# SKYROCKET1.net
KiCad netlist of a schematic drawn in EAGLE
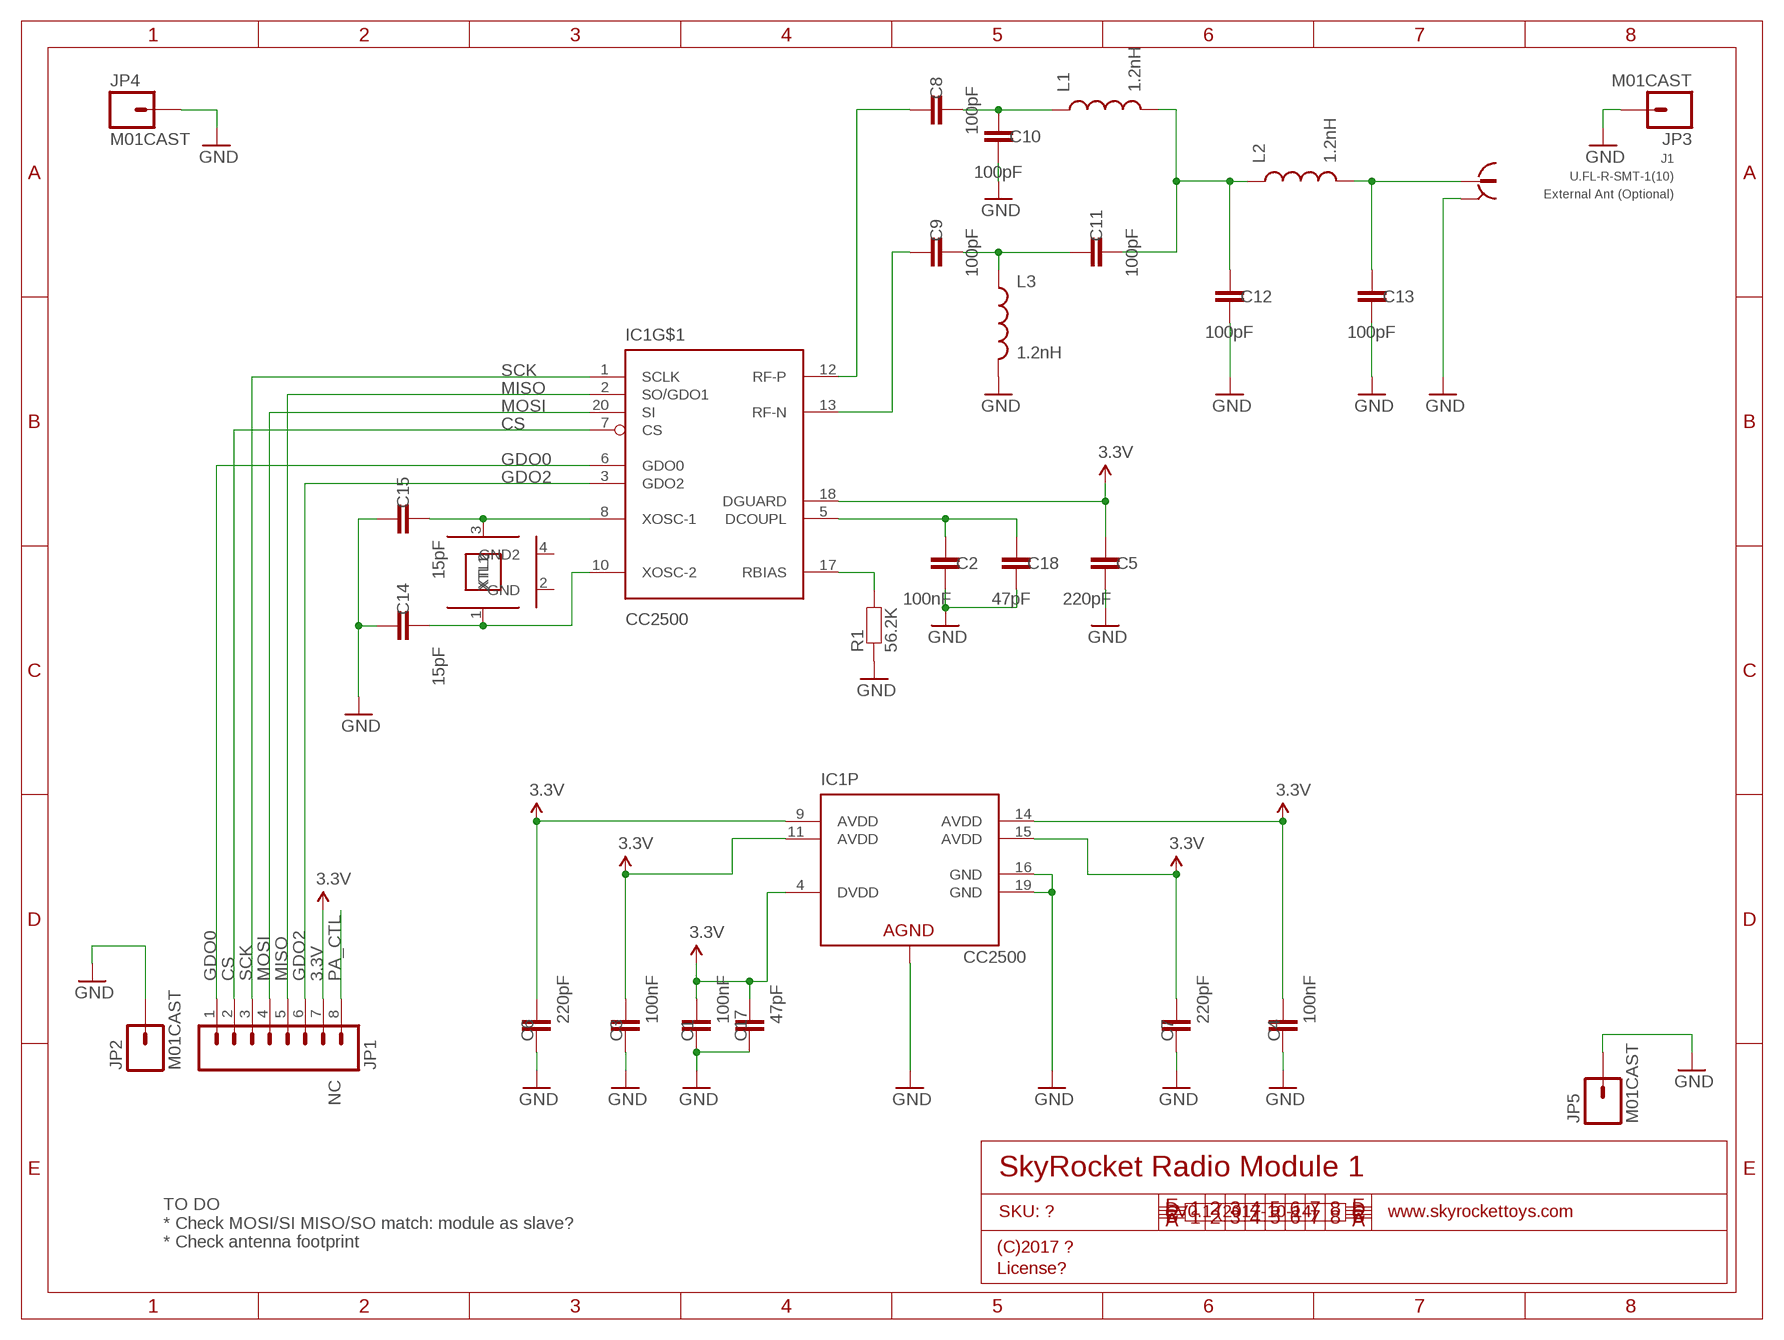
[diagram p0: schematic, sheet 1]

(export (version "E")
  (design (tool "Eeschema 10.0.6"))
  (components
    (comp (ref "C1")
      (value "100nF")
      (footprint "eagle-import:0201")
      (libsource (lib "eagle-import") (part "CAP0201"))
    )
    (comp (ref "C2")
      (value "100nF")
      (footprint "eagle-import:0201")
      (libsource (lib "eagle-import") (part "CAP0201"))
    )
    (comp (ref "C3")
      (value "100nF")
      (footprint "eagle-import:0201")
      (libsource (lib "eagle-import") (part "CAP0201"))
    )
    (comp (ref "C4")
      (value "100nF")
      (footprint "eagle-import:0201")
      (libsource (lib "eagle-import") (part "CAP0201"))
    )
    (comp (ref "C5")
      (value "220pF")
      (footprint "eagle-import:0201")
      (libsource (lib "eagle-import") (part "CAP0201"))
    )
    (comp (ref "C6")
      (value "220pF")
      (footprint "eagle-import:0201")
      (libsource (lib "eagle-import") (part "CAP0201"))
    )
    (comp (ref "C7")
      (value "220pF")
      (footprint "eagle-import:0201")
      (libsource (lib "eagle-import") (part "CAP0201"))
    )
    (comp (ref "C8")
      (value "100pF")
      (footprint "eagle-import:0201")
      (libsource (lib "eagle-import") (part "CAP0201"))
    )
    (comp (ref "C9")
      (value "100pF")
      (footprint "eagle-import:0201")
      (libsource (lib "eagle-import") (part "CAP0201"))
    )
    (comp (ref "C10")
      (value "100pF")
      (footprint "eagle-import:0201")
      (libsource (lib "eagle-import") (part "CAP0201"))
    )
    (comp (ref "C11")
      (value "100pF")
      (footprint "eagle-import:0201")
      (libsource (lib "eagle-import") (part "CAP0201"))
    )
    (comp (ref "C12")
      (value "100pF")
      (footprint "eagle-import:0201")
      (libsource (lib "eagle-import") (part "CAP0201"))
    )
    (comp (ref "C13")
      (value "100pF")
      (footprint "eagle-import:0201")
      (libsource (lib "eagle-import") (part "CAP0201"))
    )
    (comp (ref "C14")
      (value "15pF")
      (footprint "eagle-import:0201")
      (libsource (lib "eagle-import") (part "CAP0201"))
    )
    (comp (ref "C15")
      (value "15pF")
      (footprint "eagle-import:0201")
      (libsource (lib "eagle-import") (part "CAP0201"))
    )
    (comp (ref "C17")
      (value "47pF")
      (footprint "eagle-import:0201")
      (libsource (lib "eagle-import") (part "CAP0201"))
    )
    (comp (ref "C18")
      (value "47pF")
      (footprint "eagle-import:0201")
      (libsource (lib "eagle-import") (part "CAP0201"))
    )
    (comp (ref "IC1")
      (value "CC2500")
      (footprint "eagle-import:QFN50P400X400X90-21N")
      (libsource (lib "eagle-import") (part "CC2500"))
    )
    (comp (ref "J1")
      (value "U.FL-R-SMT-1(10)")
      (footprint "eagle-import:UFL")
      (fields (field (name "NOTE") "External Ant (Optional)"))
      (libsource (lib "eagle-import") (part "UFL"))
    )
    (comp (ref "JP1")
      (value "M08CAST")
      (footprint "eagle-import:1X08_CASTELLATED_1.25")
      (libsource (lib "eagle-import") (part "M08CAST"))
    )
    (comp (ref "JP2")
      (value "M01CAST")
      (footprint "eagle-import:1X01_CASTELLATED_1.25")
      (libsource (lib "eagle-import") (part "M01CAST"))
    )
    (comp (ref "JP3")
      (value "M01CAST")
      (footprint "eagle-import:1X01_CASTELLATED_1.25")
      (libsource (lib "eagle-import") (part "M01CAST"))
    )
    (comp (ref "JP4")
      (value "M01CAST")
      (footprint "eagle-import:1X01_CASTELLATED_1.25")
      (libsource (lib "eagle-import") (part "M01CAST"))
    )
    (comp (ref "JP5")
      (value "M01CAST")
      (footprint "eagle-import:1X01_CASTELLATED_1.25")
      (libsource (lib "eagle-import") (part "M01CAST"))
    )
    (comp (ref "L1")
      (value "1.2nH")
      (footprint "eagle-import:0603")
      (libsource (lib "eagle-import") (part "INDUCTOR20603"))
    )
    (comp (ref "L2")
      (value "1.2nH")
      (footprint "eagle-import:0603")
      (libsource (lib "eagle-import") (part "INDUCTOR20603"))
    )
    (comp (ref "L3")
      (value "1.2nH")
      (footprint "eagle-import:0603")
      (libsource (lib "eagle-import") (part "INDUCTOR20603"))
    )
    (comp (ref "R1")
      (value "56.2K")
      (footprint "eagle-import:0201")
      (libsource (lib "eagle-import") (part "RESISTOR0201"))
    )
    (comp (ref "XTL1")
      (value "26MHz")
      (footprint "eagle-import:CRYSTAL-SMD-3X2")
      (libsource (lib "eagle-import") (part "CRYSTAL-GND3X2"))
    )
  )
  (nets
    (net (code "1") (name "/CS") (class "Default")
      (node (ref "IC1") (pin "7") (pinfunction "CS_7") (pintype "input"))
      (node (ref "JP1") (pin "2") (pinfunction "2_2") (pintype "passive"))
    )
    (net (code "2") (name "/GDO0") (class "Default")
      (node (ref "IC1") (pin "6") (pinfunction "GDO0_6") (pintype "output"))
      (node (ref "JP1") (pin "1") (pinfunction "1_1") (pintype "passive"))
    )
    (net (code "3") (name "/GDO2") (class "Default")
      (node (ref "IC1") (pin "3") (pinfunction "GDO2_3") (pintype "output"))
      (node (ref "JP1") (pin "6") (pinfunction "6_6") (pintype "passive"))
    )
    (net (code "4") (name "/MISO") (class "Default")
      (node (ref "IC1") (pin "2") (pinfunction "SO/GDO1_2") (pintype "output"))
      (node (ref "JP1") (pin "5") (pinfunction "5_5") (pintype "passive"))
    )
    (net (code "5") (name "/MOSI") (class "Default")
      (node (ref "IC1") (pin "20") (pinfunction "SI_20") (pintype "input"))
      (node (ref "JP1") (pin "4") (pinfunction "4_4") (pintype "passive"))
    )
    (net (code "6") (name "/PA_CTL") (class "Default")
      (node (ref "JP1") (pin "8") (pinfunction "8_8") (pintype "passive"))
    )
    (net (code "7") (name "/SCK") (class "Default")
      (node (ref "IC1") (pin "1") (pinfunction "SCLK_1") (pintype "input"))
      (node (ref "JP1") (pin "3") (pinfunction "3_3") (pintype "passive"))
    )
    (net (code "8") (name "3.3V") (class "Default")
      (node (ref "C1") (pin "2") (pinfunction "2_2") (pintype "passive"))
      (node (ref "C17") (pin "2") (pinfunction "2_2") (pintype "passive"))
      (node (ref "C3") (pin "2") (pinfunction "2_2") (pintype "passive"))
      (node (ref "C4") (pin "2") (pinfunction "2_2") (pintype "passive"))
      (node (ref "C5") (pin "1") (pinfunction "1_1") (pintype "passive"))
      (node (ref "C6") (pin "2") (pinfunction "2_2") (pintype "passive"))
      (node (ref "C7") (pin "2") (pinfunction "2_2") (pintype "passive"))
      (node (ref "IC1") (pin "11") (pinfunction "AVDD_11") (pintype "power_in"))
      (node (ref "IC1") (pin "14") (pinfunction "AVDD_14") (pintype "power_in"))
      (node (ref "IC1") (pin "15") (pinfunction "AVDD_15") (pintype "power_in"))
      (node (ref "IC1") (pin "18") (pinfunction "DGUARD_18") (pintype "power_in"))
      (node (ref "IC1") (pin "4") (pinfunction "DVDD_4") (pintype "power_in"))
      (node (ref "IC1") (pin "9") (pinfunction "AVDD_9") (pintype "power_in"))
      (node (ref "JP1") (pin "7") (pinfunction "7_7") (pintype "passive"))
    )
    (net (code "9") (name "GND") (class "Default")
      (node (ref "C1") (pin "1") (pinfunction "1_1") (pintype "passive"))
      (node (ref "C10") (pin "2") (pinfunction "2_2") (pintype "passive"))
      (node (ref "C12") (pin "2") (pinfunction "2_2") (pintype "passive"))
      (node (ref "C13") (pin "2") (pinfunction "2_2") (pintype "passive"))
      (node (ref "C14") (pin "1") (pinfunction "1_1") (pintype "passive"))
      (node (ref "C15") (pin "1") (pinfunction "1_1") (pintype "passive"))
      (node (ref "C17") (pin "1") (pinfunction "1_1") (pintype "passive"))
      (node (ref "C18") (pin "2") (pinfunction "2_2") (pintype "passive"))
      (node (ref "C2") (pin "2") (pinfunction "2_2") (pintype "passive"))
      (node (ref "C3") (pin "1") (pinfunction "1_1") (pintype "passive"))
      (node (ref "C4") (pin "1") (pinfunction "1_1") (pintype "passive"))
      (node (ref "C5") (pin "2") (pinfunction "2_2") (pintype "passive"))
      (node (ref "C6") (pin "1") (pinfunction "1_1") (pintype "passive"))
      (node (ref "C7") (pin "1") (pinfunction "1_1") (pintype "passive"))
      (node (ref "IC1") (pin "16") (pinfunction "GND_16") (pintype "power_in"))
      (node (ref "IC1") (pin "19") (pinfunction "GND_19") (pintype "power_in"))
      (node (ref "IC1") (pin "21") (pinfunction "AGND_21") (pintype "power_in"))
      (node (ref "J1") (pin "GND") (pinfunction "GND_GND") (pintype "power_in"))
      (node (ref "J1") (pin "GND@1") (pinfunction "GND_GND@1") (pintype "power_in"))
      (node (ref "JP2") (pin "1") (pinfunction "1_1") (pintype "passive"))
      (node (ref "JP3") (pin "1") (pinfunction "1_1") (pintype "passive"))
      (node (ref "JP4") (pin "1") (pinfunction "1_1") (pintype "passive"))
      (node (ref "JP5") (pin "1") (pinfunction "1_1") (pintype "passive"))
      (node (ref "L3") (pin "2") (pinfunction "2_2") (pintype "passive"))
      (node (ref "R1") (pin "1") (pinfunction "1_1") (pintype "passive"))
    )
    (net (code "10") (name "Net-(C10-Pad1)") (class "Default")
      (node (ref "C10") (pin "1") (pinfunction "1_1") (pintype "passive"))
      (node (ref "C8") (pin "2") (pinfunction "2_2") (pintype "passive"))
      (node (ref "L1") (pin "1") (pinfunction "1_1") (pintype "passive"))
    )
    (net (code "11") (name "Net-(C11-Pad1)") (class "Default")
      (node (ref "C11") (pin "1") (pinfunction "1_1") (pintype "passive"))
      (node (ref "C9") (pin "2") (pinfunction "2_2") (pintype "passive"))
      (node (ref "L3") (pin "1") (pinfunction "1_1") (pintype "passive"))
    )
    (net (code "12") (name "Net-(C11-Pad2)") (class "Default")
      (node (ref "C11") (pin "2") (pinfunction "2_2") (pintype "passive"))
      (node (ref "C12") (pin "1") (pinfunction "1_1") (pintype "passive"))
      (node (ref "L1") (pin "2") (pinfunction "2_2") (pintype "passive"))
      (node (ref "L2") (pin "1") (pinfunction "1_1") (pintype "passive"))
    )
    (net (code "13") (name "Net-(C13-Pad1)") (class "Default")
      (node (ref "C13") (pin "1") (pinfunction "1_1") (pintype "passive"))
      (node (ref "J1") (pin "SIG") (pinfunction "SIG_SIG") (pintype "passive"))
      (node (ref "L2") (pin "2") (pinfunction "2_2") (pintype "passive"))
    )
    (net (code "14") (name "Net-(IC1A-DCOUPL)") (class "Default")
      (node (ref "C18") (pin "1") (pinfunction "1_1") (pintype "passive"))
      (node (ref "C2") (pin "1") (pinfunction "1_1") (pintype "passive"))
      (node (ref "IC1") (pin "5") (pinfunction "DCOUPL_5") (pintype "power_in"))
    )
    (net (code "15") (name "Net-(IC1A-RBIAS)") (class "Default")
      (node (ref "IC1") (pin "17") (pinfunction "RBIAS_17") (pintype "bidirectional"))
      (node (ref "R1") (pin "2") (pinfunction "2_2") (pintype "passive"))
    )
    (net (code "16") (name "Net-(IC1A-RF-N)") (class "Default")
      (node (ref "C9") (pin "1") (pinfunction "1_1") (pintype "passive"))
      (node (ref "IC1") (pin "13") (pinfunction "RF-N_13") (pintype "bidirectional"))
    )
    (net (code "17") (name "Net-(IC1A-RF-P)") (class "Default")
      (node (ref "C8") (pin "1") (pinfunction "1_1") (pintype "passive"))
      (node (ref "IC1") (pin "12") (pinfunction "RF-P_12") (pintype "bidirectional"))
    )
    (net (code "18") (name "Net-(IC1A-XOSC-1)") (class "Default")
      (node (ref "C15") (pin "2") (pinfunction "2_2") (pintype "passive"))
      (node (ref "IC1") (pin "8") (pinfunction "XOSC-1_8") (pintype "input"))
      (node (ref "XTL1") (pin "3") (pinfunction "XTL2_3") (pintype "bidirectional"))
    )
    (net (code "19") (name "Net-(IC1A-XOSC-2)") (class "Default")
      (node (ref "C14") (pin "2") (pinfunction "2_2") (pintype "passive"))
      (node (ref "IC1") (pin "10") (pinfunction "XOSC-2_10") (pintype "output"))
      (node (ref "XTL1") (pin "1") (pinfunction "XTL1_1") (pintype "bidirectional"))
    )
    (net (code "20") (name "unconnected-(XTL1-GND-Pad2)") (class "Default")
      (node (ref "XTL1") (pin "2") (pinfunction "GND_2") (pintype "bidirectional"))
    )
    (net (code "21") (name "unconnected-(XTL1-GND2-Pad4)") (class "Default")
      (node (ref "XTL1") (pin "4") (pinfunction "GND2_4") (pintype "bidirectional"))
    )
  )
)
